# capsense.net
KiCad netlist of a schematic drawn in EAGLE
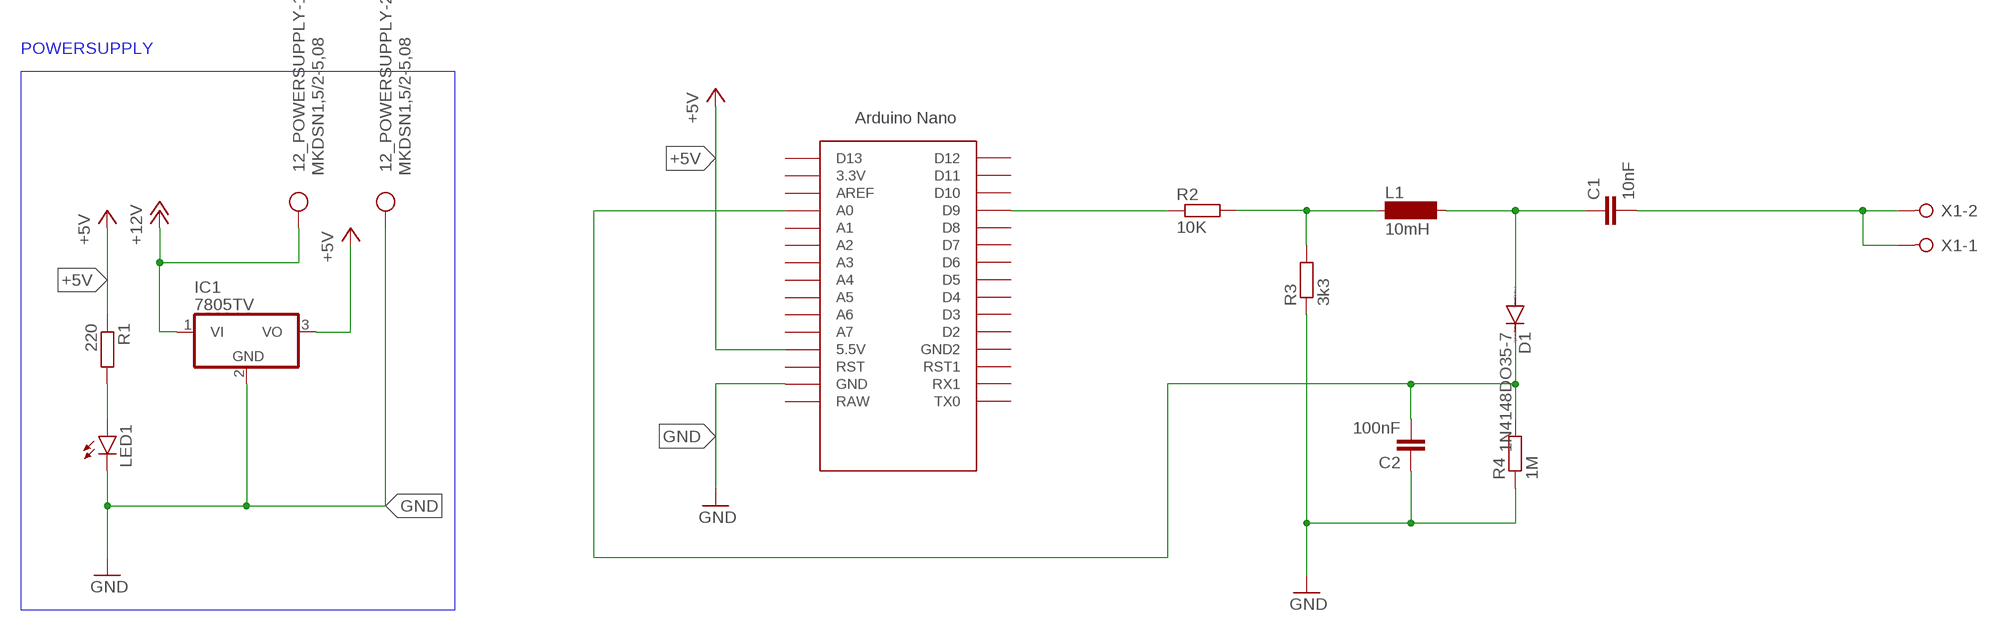
[diagram p0: schematic, sheet 1]

(export (version "E")
  (design (tool "Eeschema 10.0.6"))
  (components
    (comp (ref "12_POWERSUPPLY")
      (value "MKDSN1,5/2-5,08")
      (footprint "eagle-import:MKDSN1,5_2-5,08")
      (libsource (lib "eagle-import") (part "MKDSN1,5/2-5,08"))
    )
    (comp (ref "C1")
      (value "10nF")
      (footprint "eagle-import:C050-024X044")
      (libsource (lib "eagle-import") (part "C-EU050-024X044"))
    )
    (comp (ref "C2")
      (value "100nF")
      (footprint "eagle-import:C050-024X044")
      (libsource (lib "eagle-import") (part "C-EU050-024X044"))
    )
    (comp (ref "D1")
      (value "1N4148DO35-7")
      (footprint "eagle-import:DO35-7")
      (libsource (lib "eagle-import") (part "1N4148DO35-7"))
    )
    (comp (ref "IC1")
      (value "7805TV")
      (footprint "eagle-import:TO220V")
      (libsource (lib "eagle-import") (part "78TV05"))
    )
    (comp (ref "L1")
      (value "10mH")
      (footprint "eagle-import:BS11")
      (libsource (lib "eagle-import") (part "BS11"))
    )
    (comp (ref "LED1")
      (value "LED3MM")
      (footprint "eagle-import:LED3MM")
      (libsource (lib "eagle-import") (part "LED3MM"))
    )
    (comp (ref "R1")
      (value "220")
      (footprint "eagle-import:R0805")
      (libsource (lib "eagle-import") (part "R-EU_R0805"))
    )
    (comp (ref "R2")
      (value "10K")
      (footprint "eagle-import:0207_7")
      (libsource (lib "eagle-import") (part "R-EU_0207/7"))
    )
    (comp (ref "R3")
      (value "3k3")
      (footprint "eagle-import:0207_7")
      (libsource (lib "eagle-import") (part "R-EU_0207/7"))
    )
    (comp (ref "R4")
      (value "1M")
      (footprint "eagle-import:0207_7")
      (libsource (lib "eagle-import") (part "R-EU_0207/7"))
    )
    (comp (ref "U$1")
      (value "NANO")
      (footprint "eagle-import:NANO")
      (libsource (lib "eagle-import") (part "NANO"))
    )
    (comp (ref "X1")
      (value "W237-02P")
      (footprint "eagle-import:W237-132")
      (libsource (lib "eagle-import") (part "W237-02P"))
    )
  )
  (nets
    (net (code "1") (name "+5V") (class "Default")
      (node (ref "IC1") (pin "3") (pinfunction "VO_3") (pintype "passive"))
      (node (ref "R1") (pin "1") (pinfunction "1_1") (pintype "passive"))
      (node (ref "U$1") (pin "5V") (pinfunction "5.5V_5V") (pintype "bidirectional"))
    )
    (net (code "2") (name "+12V") (class "Default")
      (node (ref "12_POWERSUPPLY") (pin "1") (pinfunction "KL_1") (pintype "passive"))
      (node (ref "IC1") (pin "1") (pinfunction "VI_1") (pintype "input"))
    )
    (net (code "3") (name "GND") (class "Default")
      (node (ref "12_POWERSUPPLY") (pin "2") (pinfunction "KL_2") (pintype "passive"))
      (node (ref "C2") (pin "1") (pinfunction "1_1") (pintype "passive"))
      (node (ref "IC1") (pin "2") (pinfunction "GND_2") (pintype "passive"))
      (node (ref "LED1") (pin "K") (pinfunction "C_K") (pintype "passive"))
      (node (ref "R3") (pin "1") (pinfunction "1_1") (pintype "passive"))
      (node (ref "R4") (pin "1") (pinfunction "1_1") (pintype "passive"))
      (node (ref "U$1") (pin "GND") (pinfunction "GND_GND") (pintype "bidirectional"))
    )
    (net (code "4") (name "Net-(C1-Pad1)") (class "Default")
      (node (ref "C1") (pin "1") (pinfunction "1_1") (pintype "passive"))
      (node (ref "D1") (pin "A") (pinfunction "A_A") (pintype "passive"))
      (node (ref "L1") (pin "2") (pinfunction "2_2") (pintype "passive"))
    )
    (net (code "5") (name "Net-(C2-Pad2)") (class "Default")
      (node (ref "C2") (pin "2") (pinfunction "2_2") (pintype "passive"))
      (node (ref "D1") (pin "C") (pinfunction "C_C") (pintype "passive"))
      (node (ref "R4") (pin "2") (pinfunction "2_2") (pintype "passive"))
      (node (ref "U$1") (pin "A0") (pinfunction "A0_A0") (pintype "bidirectional"))
    )
    (net (code "6") (name "Net-(L1-Pad1)") (class "Default")
      (node (ref "L1") (pin "1") (pinfunction "1_1") (pintype "passive"))
      (node (ref "R2") (pin "2") (pinfunction "2_2") (pintype "passive"))
      (node (ref "R3") (pin "2") (pinfunction "2_2") (pintype "passive"))
    )
    (net (code "7") (name "Net-(LED1-PadA)") (class "Default")
      (node (ref "LED1") (pin "A") (pinfunction "A_A") (pintype "passive"))
      (node (ref "R1") (pin "2") (pinfunction "2_2") (pintype "passive"))
    )
    (net (code "8") (name "Net-(R2-Pad1)") (class "Default")
      (node (ref "R2") (pin "1") (pinfunction "1_1") (pintype "passive"))
      (node (ref "U$1") (pin "D9") (pinfunction "D9_D9") (pintype "bidirectional"))
    )
    (net (code "9") (name "Net-(X1A-KL)") (class "Default")
      (node (ref "C1") (pin "2") (pinfunction "2_2") (pintype "passive"))
      (node (ref "X1") (pin "1") (pinfunction "KL_1") (pintype "passive"))
      (node (ref "X1") (pin "2") (pinfunction "KL_2") (pintype "passive"))
    )
    (net (code "10") (name "unconnected-(U$1-GND2-PadGND1)") (class "Default")
      (node (ref "U$1") (pin "GND1") (pinfunction "GND2_GND1") (pintype "bidirectional"))
    )
    (net (code "11") (name "unconnected-(U$1-Pad3.3V)") (class "Default")
      (node (ref "U$1") (pin "3.3V") (pinfunction "3.3V_3.3V") (pintype "bidirectional"))
    )
    (net (code "12") (name "unconnected-(U$1-PadA1)") (class "Default")
      (node (ref "U$1") (pin "A1") (pinfunction "A1_A1") (pintype "bidirectional"))
    )
    (net (code "13") (name "unconnected-(U$1-PadA2)") (class "Default")
      (node (ref "U$1") (pin "A2") (pinfunction "A2_A2") (pintype "bidirectional"))
    )
    (net (code "14") (name "unconnected-(U$1-PadA3)") (class "Default")
      (node (ref "U$1") (pin "A3") (pinfunction "A3_A3") (pintype "bidirectional"))
    )
    (net (code "15") (name "unconnected-(U$1-PadA4)") (class "Default")
      (node (ref "U$1") (pin "A4") (pinfunction "A4_A4") (pintype "bidirectional"))
    )
    (net (code "16") (name "unconnected-(U$1-PadA5)") (class "Default")
      (node (ref "U$1") (pin "A5") (pinfunction "A5_A5") (pintype "bidirectional"))
    )
    (net (code "17") (name "unconnected-(U$1-PadA6)") (class "Default")
      (node (ref "U$1") (pin "A6") (pinfunction "A6_A6") (pintype "bidirectional"))
    )
    (net (code "18") (name "unconnected-(U$1-PadA7)") (class "Default")
      (node (ref "U$1") (pin "A7") (pinfunction "A7_A7") (pintype "bidirectional"))
    )
    (net (code "19") (name "unconnected-(U$1-PadAREF)") (class "Default")
      (node (ref "U$1") (pin "AREF") (pinfunction "AREF_AREF") (pintype "bidirectional"))
    )
    (net (code "20") (name "unconnected-(U$1-PadD2)") (class "Default")
      (node (ref "U$1") (pin "D2") (pinfunction "D2_D2") (pintype "bidirectional"))
    )
    (net (code "21") (name "unconnected-(U$1-PadD3)") (class "Default")
      (node (ref "U$1") (pin "D3") (pinfunction "D3_D3") (pintype "bidirectional"))
    )
    (net (code "22") (name "unconnected-(U$1-PadD4)") (class "Default")
      (node (ref "U$1") (pin "D4") (pinfunction "D4_D4") (pintype "bidirectional"))
    )
    (net (code "23") (name "unconnected-(U$1-PadD5)") (class "Default")
      (node (ref "U$1") (pin "D5") (pinfunction "D5_D5") (pintype "bidirectional"))
    )
    (net (code "24") (name "unconnected-(U$1-PadD6)") (class "Default")
      (node (ref "U$1") (pin "D6") (pinfunction "D6_D6") (pintype "bidirectional"))
    )
    (net (code "25") (name "unconnected-(U$1-PadD7)") (class "Default")
      (node (ref "U$1") (pin "D7") (pinfunction "D7_D7") (pintype "bidirectional"))
    )
    (net (code "26") (name "unconnected-(U$1-PadD8)") (class "Default")
      (node (ref "U$1") (pin "D8") (pinfunction "D8_D8") (pintype "bidirectional"))
    )
    (net (code "27") (name "unconnected-(U$1-PadD10)") (class "Default")
      (node (ref "U$1") (pin "D10") (pinfunction "D10_D10") (pintype "bidirectional"))
    )
    (net (code "28") (name "unconnected-(U$1-PadD11)") (class "Default")
      (node (ref "U$1") (pin "D11") (pinfunction "D11_D11") (pintype "bidirectional"))
    )
    (net (code "29") (name "unconnected-(U$1-PadD12)") (class "Default")
      (node (ref "U$1") (pin "D12") (pinfunction "D12_D12") (pintype "bidirectional"))
    )
    (net (code "30") (name "unconnected-(U$1-PadD13)") (class "Default")
      (node (ref "U$1") (pin "D13") (pinfunction "D13_D13") (pintype "bidirectional"))
    )
    (net (code "31") (name "unconnected-(U$1-PadICSP1)") (class "Default")
      (node (ref "U$1") (pin "ICSP1") (pinfunction "ICSP1_ICSP1") (pintype "bidirectional"))
    )
    (net (code "32") (name "unconnected-(U$1-PadICSP2)") (class "Default")
      (node (ref "U$1") (pin "ICSP2") (pinfunction "ICSP2_ICSP2") (pintype "bidirectional"))
    )
    (net (code "33") (name "unconnected-(U$1-PadICSP3)") (class "Default")
      (node (ref "U$1") (pin "ICSP3") (pinfunction "ICSP3_ICSP3") (pintype "bidirectional"))
    )
    (net (code "34") (name "unconnected-(U$1-PadICSP4)") (class "Default")
      (node (ref "U$1") (pin "ICSP4") (pinfunction "ICSP4_ICSP4") (pintype "bidirectional"))
    )
    (net (code "35") (name "unconnected-(U$1-PadICSP5)") (class "Default")
      (node (ref "U$1") (pin "ICSP5") (pinfunction "ICSP5_ICSP5") (pintype "bidirectional"))
    )
    (net (code "36") (name "unconnected-(U$1-PadICSP6)") (class "Default")
      (node (ref "U$1") (pin "ICSP6") (pinfunction "ICSP6_ICSP6") (pintype "bidirectional"))
    )
    (net (code "37") (name "unconnected-(U$1-PadRAW)") (class "Default")
      (node (ref "U$1") (pin "RAW") (pinfunction "RAW_RAW") (pintype "bidirectional"))
    )
    (net (code "38") (name "unconnected-(U$1-PadRST)") (class "Default")
      (node (ref "U$1") (pin "RST") (pinfunction "RST_RST") (pintype "bidirectional"))
    )
    (net (code "39") (name "unconnected-(U$1-PadRST1)") (class "Default")
      (node (ref "U$1") (pin "RST1") (pinfunction "RST1_RST1") (pintype "bidirectional"))
    )
    (net (code "40") (name "unconnected-(U$1-PadRX1)") (class "Default")
      (node (ref "U$1") (pin "RX1") (pinfunction "RX1_RX1") (pintype "bidirectional"))
    )
    (net (code "41") (name "unconnected-(U$1-PadTX0)") (class "Default")
      (node (ref "U$1") (pin "TX0") (pinfunction "TX0_TX0") (pintype "bidirectional"))
    )
  )
)
